# cherry-mx-1.net
KiCad netlist of a schematic drawn in EAGLE
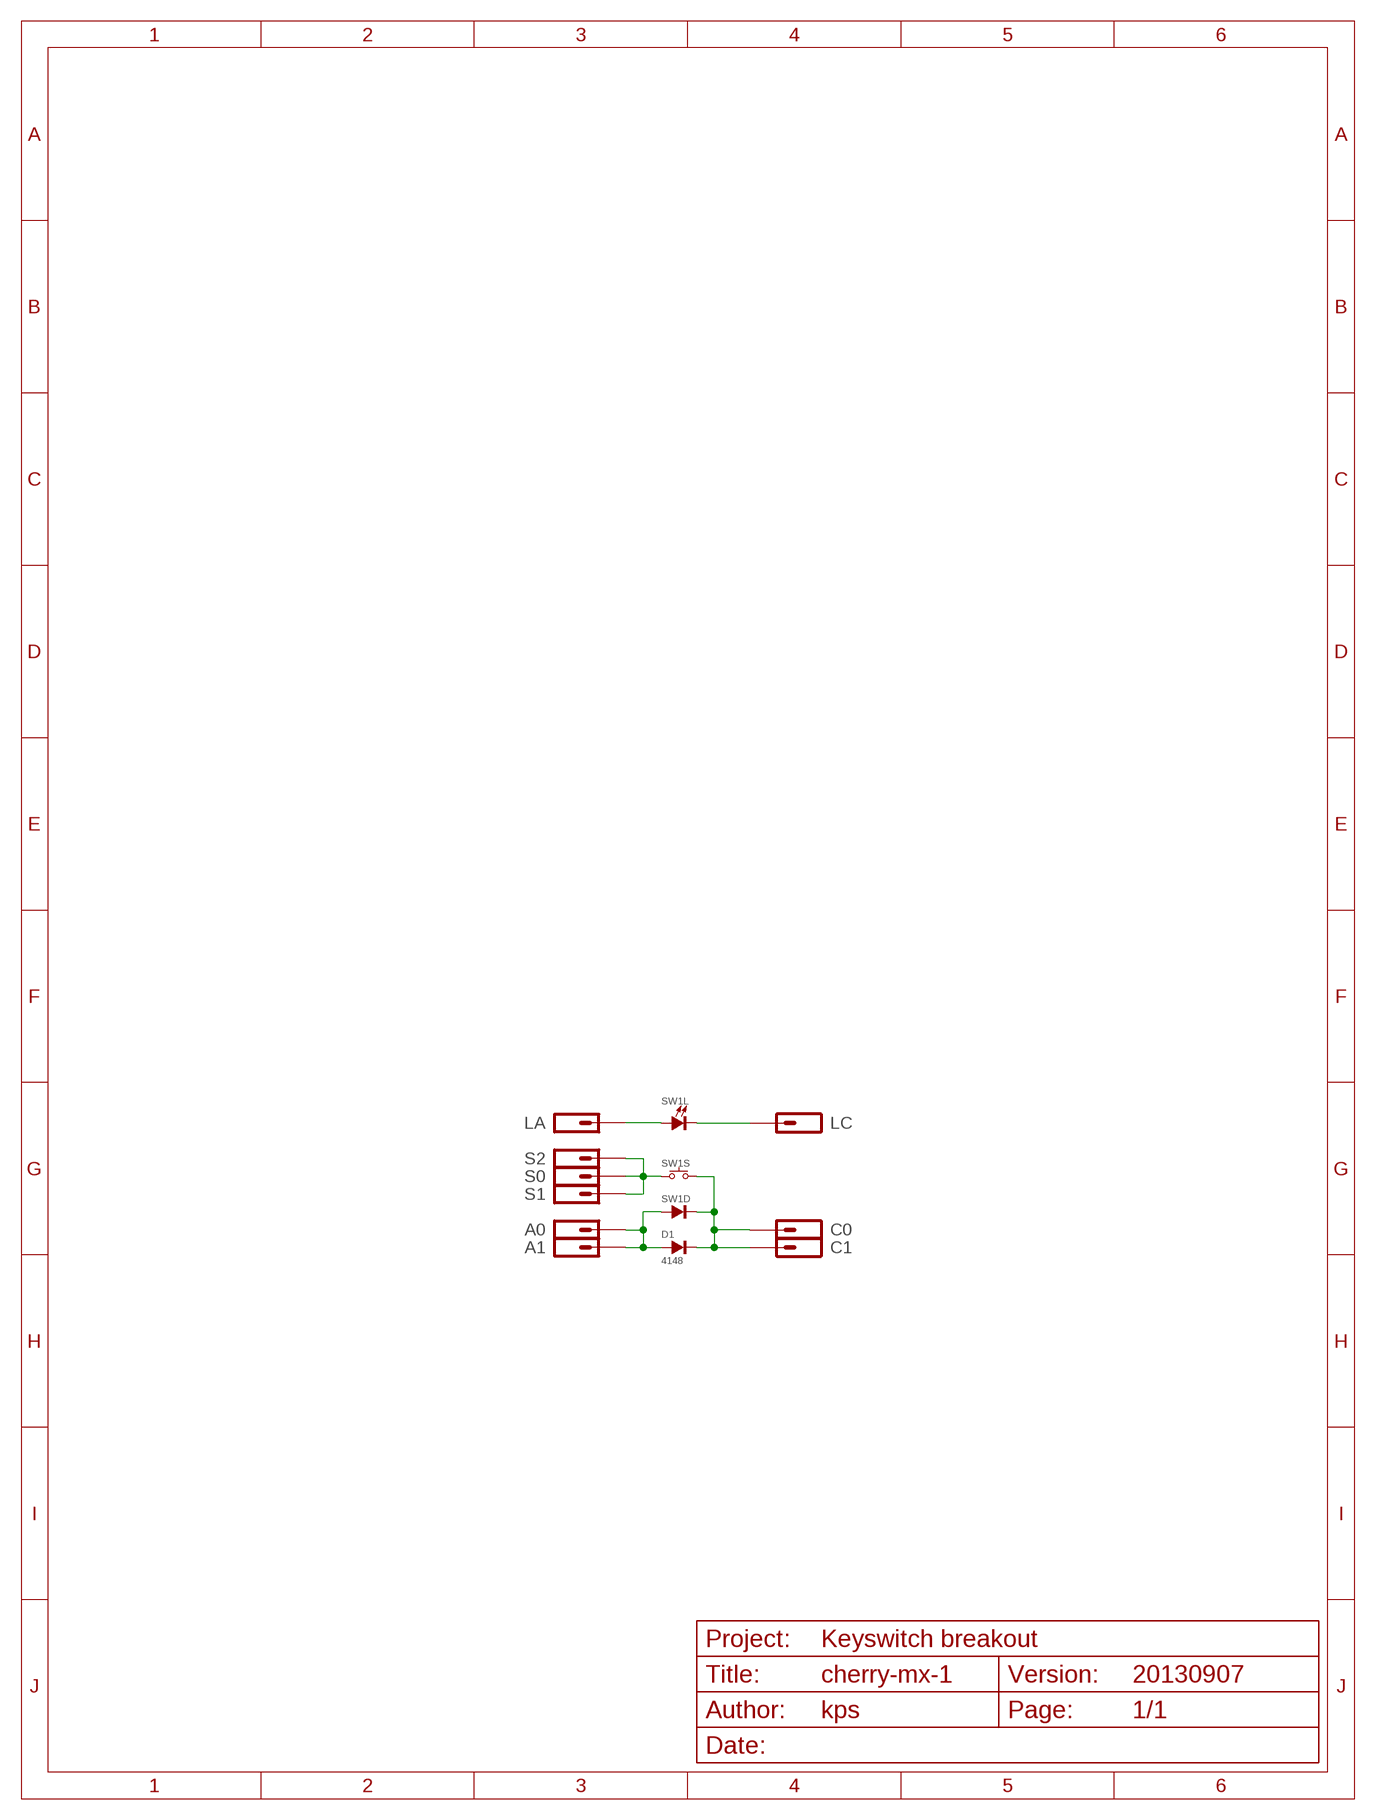
[diagram p0: schematic, sheet 1]

(export (version "E")
  (design (tool "Eeschema 10.0.6"))
  (components
    (comp (ref "A0")
      (value "J-1-SQUARE-70")
      (footprint "eagle-import:J-1-SQUARE-70")
      (libsource (lib "eagle-import") (part "J-1-SQUARE-70"))
    )
    (comp (ref "A1")
      (value "J-1-SQUARE-74")
      (footprint "eagle-import:J-1-SQUARE-74")
      (libsource (lib "eagle-import") (part "J-1-SQUARE-74"))
    )
    (comp (ref "C0")
      (value "J-1-SQUARE-70")
      (footprint "eagle-import:J-1-SQUARE-70")
      (libsource (lib "eagle-import") (part "J-1-SQUARE-70"))
    )
    (comp (ref "C1")
      (value "J-1-SQUARE-74")
      (footprint "eagle-import:J-1-SQUARE-74")
      (libsource (lib "eagle-import") (part "J-1-SQUARE-74"))
    )
    (comp (ref "D1")
      (value "4148")
      (footprint "eagle-import:SMA+SOD323-P-NOSS")
      (libsource (lib "eagle-import") (part "DIODE-SMA+SOD323-NOSS"))
    )
    (comp (ref "LA")
      (value "J-1-OCTAGON-70")
      (footprint "eagle-import:J-1-OCTAGON-70")
      (libsource (lib "eagle-import") (part "J-1-OCTAGON-70"))
    )
    (comp (ref "LC")
      (value "J-1-OCTAGON-70")
      (footprint "eagle-import:J-1-OCTAGON-70")
      (libsource (lib "eagle-import") (part "J-1-OCTAGON-70"))
    )
    (comp (ref "S0")
      (value "J-1-ROUND-70")
      (footprint "eagle-import:J-1-ROUND-70")
      (libsource (lib "eagle-import") (part "J-1-ROUND-70"))
    )
    (comp (ref "S1")
      (value "J-1-ROUND-74")
      (footprint "eagle-import:J-1-ROUND-74")
      (libsource (lib "eagle-import") (part "J-1-ROUND-74"))
    )
    (comp (ref "S2")
      (value "J-1-ROUND-74")
      (footprint "eagle-import:J-1-ROUND-74")
      (libsource (lib "eagle-import") (part "J-1-ROUND-74"))
    )
    (comp (ref "SW1")
      (value "SW-CHERRY-MX-BOTH")
      (footprint "eagle-import:SW-CHERRY-MX-BOTH")
      (libsource (lib "eagle-import") (part "SW-CHERRY-MX-BOTH"))
    )
  )
  (nets
    (net (code "1") (name "Net-(A0-Pad1)") (class "Default")
      (node (ref "A0") (pin "1") (pinfunction "1_1") (pintype "passive"))
      (node (ref "A1") (pin "1") (pinfunction "1_1") (pintype "passive"))
      (node (ref "D1") (pin "A") (pinfunction "A_A") (pintype "passive"))
      (node (ref "SW1") (pin "A") (pinfunction "A_A") (pintype "passive"))
    )
    (net (code "2") (name "Net-(SW1B-A)") (class "Default")
      (node (ref "LA") (pin "1") (pinfunction "1_1") (pintype "passive"))
      (node (ref "SW1") (pin "LA") (pinfunction "A_LA") (pintype "passive"))
    )
    (net (code "3") (name "Net-(SW1B-C)") (class "Default")
      (node (ref "LC") (pin "1") (pinfunction "1_1") (pintype "passive"))
      (node (ref "SW1") (pin "LC") (pinfunction "C_LC") (pintype "passive"))
    )
    (net (code "4") (name "Net-(SW1C-1)") (class "Default")
      (node (ref "S0") (pin "1") (pinfunction "1_1") (pintype "passive"))
      (node (ref "S1") (pin "1") (pinfunction "1_1") (pintype "passive"))
      (node (ref "S2") (pin "1") (pinfunction "1_1") (pintype "passive"))
      (node (ref "SW1") (pin "S1") (pinfunction "1_S1") (pintype "passive"))
    )
    (net (code "5") (name "Net-(SW1C-2)") (class "Default")
      (node (ref "C0") (pin "1") (pinfunction "1_1") (pintype "passive"))
      (node (ref "C1") (pin "1") (pinfunction "1_1") (pintype "passive"))
      (node (ref "D1") (pin "C") (pinfunction "C_C") (pintype "passive"))
      (node (ref "SW1") (pin "C") (pinfunction "C_C") (pintype "passive"))
      (node (ref "SW1") (pin "S2") (pinfunction "2_S2") (pintype "passive"))
    )
  )
)
